# Sheet1.net
KiCad netlist of a schematic drawn in Altium Designer
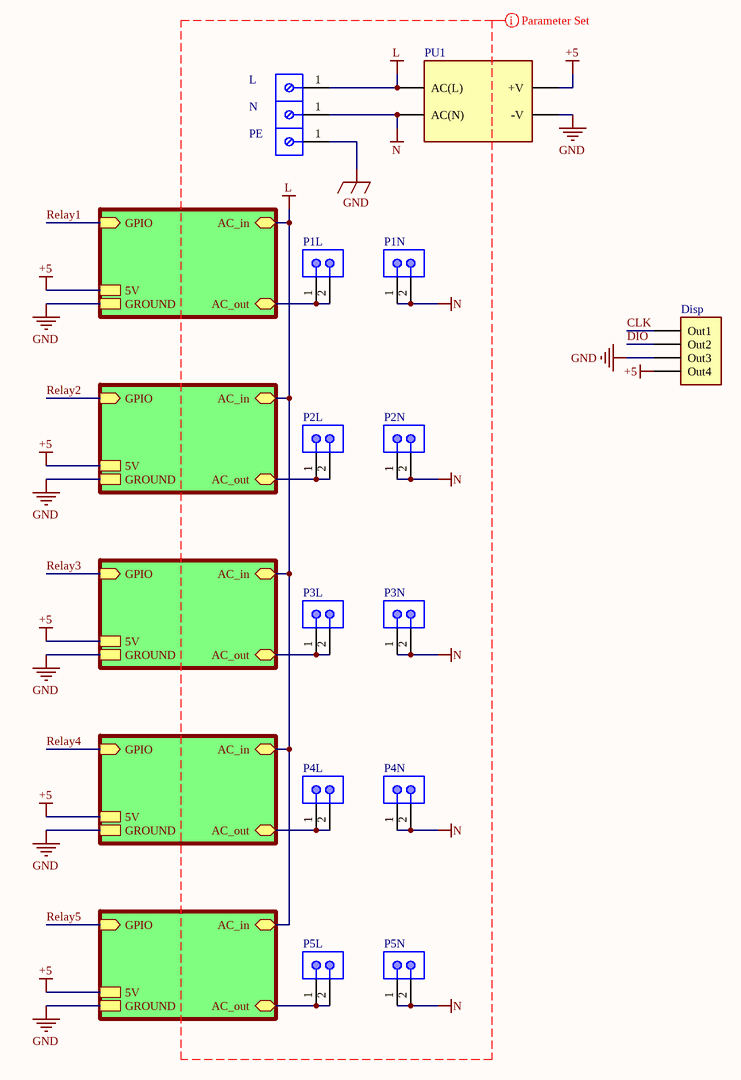
[diagram p0: Sheet1.SchDoc]

(export (version "E")
  (design (tool "Eeschema 10.0.6"))
  (components
    (comp (ref "Disp")
      (value "4Pin Connector")
      (footprint "4Pin Connector")
      (libsource (lib "Schlib1") (part "4Pin Connector"))
    )
    (comp (ref "L")
      (value "691102810001")
      (footprint "691102810001")
      (libsource (lib "Altium Content Vault") (part "TBL - 1R - 01P - Screw"))
    )
    (comp (ref "N")
      (value "691102810001")
      (footprint "691102810001")
      (libsource (lib "Altium Content Vault") (part "TBL - 1R - 01P - Screw"))
    )
    (comp (ref "P1L")
      (value "1287-ST")
      (footprint "KSTN-1287-ST")
      (description "PC Sturdi-Mount Quick-Fit Terminal, Vertical, Male, 2-Pin THD, Bulk")
      (fields (field (name "MANUFACTURER") "Keystone"))
      (libsource (lib "Altium Content Vault") (part "CN-1P-M-R2"))
    )
    (comp (ref "P1N")
      (value "1287-ST")
      (footprint "KSTN-1287-ST")
      (description "PC Sturdi-Mount Quick-Fit Terminal, Vertical, Male, 2-Pin THD, Bulk")
      (fields (field (name "MANUFACTURER") "Keystone"))
      (libsource (lib "Altium Content Vault") (part "CN-1P-M-R2"))
    )
    (comp (ref "P2L")
      (value "1287-ST")
      (footprint "KSTN-1287-ST")
      (description "PC Sturdi-Mount Quick-Fit Terminal, Vertical, Male, 2-Pin THD, Bulk")
      (fields (field (name "MANUFACTURER") "Keystone"))
      (libsource (lib "Altium Content Vault") (part "CN-1P-M-R2"))
    )
    (comp (ref "P2N")
      (value "1287-ST")
      (footprint "KSTN-1287-ST")
      (description "PC Sturdi-Mount Quick-Fit Terminal, Vertical, Male, 2-Pin THD, Bulk")
      (fields (field (name "MANUFACTURER") "Keystone"))
      (libsource (lib "Altium Content Vault") (part "CN-1P-M-R2"))
    )
    (comp (ref "P3L")
      (value "1287-ST")
      (footprint "KSTN-1287-ST")
      (description "PC Sturdi-Mount Quick-Fit Terminal, Vertical, Male, 2-Pin THD, Bulk")
      (fields (field (name "MANUFACTURER") "Keystone"))
      (libsource (lib "Altium Content Vault") (part "CN-1P-M-R2"))
    )
    (comp (ref "P3N")
      (value "1287-ST")
      (footprint "KSTN-1287-ST")
      (description "PC Sturdi-Mount Quick-Fit Terminal, Vertical, Male, 2-Pin THD, Bulk")
      (fields (field (name "MANUFACTURER") "Keystone"))
      (libsource (lib "Altium Content Vault") (part "CN-1P-M-R2"))
    )
    (comp (ref "P4L")
      (value "1287-ST")
      (footprint "KSTN-1287-ST")
      (description "PC Sturdi-Mount Quick-Fit Terminal, Vertical, Male, 2-Pin THD, Bulk")
      (fields (field (name "MANUFACTURER") "Keystone"))
      (libsource (lib "Altium Content Vault") (part "CN-1P-M-R2"))
    )
    (comp (ref "P4N")
      (value "1287-ST")
      (footprint "KSTN-1287-ST")
      (description "PC Sturdi-Mount Quick-Fit Terminal, Vertical, Male, 2-Pin THD, Bulk")
      (fields (field (name "MANUFACTURER") "Keystone"))
      (libsource (lib "Altium Content Vault") (part "CN-1P-M-R2"))
    )
    (comp (ref "P5L")
      (value "1287-ST")
      (footprint "KSTN-1287-ST")
      (description "PC Sturdi-Mount Quick-Fit Terminal, Vertical, Male, 2-Pin THD, Bulk")
      (fields (field (name "MANUFACTURER") "Keystone"))
      (libsource (lib "Altium Content Vault") (part "CN-1P-M-R2"))
    )
    (comp (ref "P5N")
      (value "1287-ST")
      (footprint "KSTN-1287-ST")
      (description "PC Sturdi-Mount Quick-Fit Terminal, Vertical, Male, 2-Pin THD, Bulk")
      (fields (field (name "MANUFACTURER") "Keystone"))
      (libsource (lib "Altium Content Vault") (part "CN-1P-M-R2"))
    )
    (comp (ref "PE")
      (value "691102810001")
      (footprint "691102810001")
      (libsource (lib "Altium Content Vault") (part "TBL - 1R - 01P - Screw"))
    )
    (comp (ref "PU1")
      (value "Netzteil")
      (footprint "Netzteil")
      (description "IRM-05-5")
      (libsource (lib "Schlib1") (part "Netzteil"))
    )
  )
  (nets
    (net (code "1") (name "+5") (class "Default")
      (node (ref "Disp") (pin "4") (pinfunction "Out4_4") (pintype "passive"))
      (node (ref "PU1") (pin "VPOS") (pinfunction "+V_VPOS") (pintype "passive"))
    )
    (net (code "2") (name "/AC_out") (class "Default")
      (node (ref "P5L") (pin "1") (pinfunction "1_1") (pintype "passive"))
      (node (ref "P5L") (pin "2") (pinfunction "2_2") (pintype "passive"))
    )
    (net (code "3") (name "/AC_out_1") (class "Default")
      (node (ref "P2L") (pin "1") (pinfunction "1_1") (pintype "passive"))
      (node (ref "P2L") (pin "2") (pinfunction "2_2") (pintype "passive"))
    )
    (net (code "4") (name "/AC_out_2") (class "Default")
      (node (ref "P1L") (pin "1") (pinfunction "1_1") (pintype "passive"))
      (node (ref "P1L") (pin "2") (pinfunction "2_2") (pintype "passive"))
    )
    (net (code "5") (name "/AC_out_3") (class "Default")
      (node (ref "P3L") (pin "1") (pinfunction "1_1") (pintype "passive"))
      (node (ref "P3L") (pin "2") (pinfunction "2_2") (pintype "passive"))
    )
    (net (code "6") (name "/AC_out_4") (class "Default")
      (node (ref "P4L") (pin "1") (pinfunction "1_1") (pintype "passive"))
      (node (ref "P4L") (pin "2") (pinfunction "2_2") (pintype "passive"))
    )
    (net (code "7") (name "/CLK") (class "Default")
      (node (ref "Disp") (pin "1") (pinfunction "Out1_1") (pintype "passive"))
    )
    (net (code "8") (name "/DIO") (class "Default")
      (node (ref "Disp") (pin "2") (pinfunction "Out2_2") (pintype "passive"))
    )
    (net (code "14") (name "GND") (class "Default")
      (node (ref "Disp") (pin "3") (pinfunction "Out3_3") (pintype "passive"))
      (node (ref "PE") (pin "1") (pinfunction "1_1") (pintype "passive"))
      (node (ref "PU1") (pin "VNEG") (pinfunction "-V_VNEG") (pintype "passive"))
    )
    (net (code "15") (name "L") (class "Default")
      (node (ref "L") (pin "1") (pinfunction "1_1") (pintype "passive"))
      (node (ref "PU1") (pin "AC/L") (pinfunction "AC(L)_AC/L") (pintype "passive"))
    )
    (net (code "16") (name "N") (class "Default")
      (node (ref "N") (pin "1") (pinfunction "1_1") (pintype "passive"))
      (node (ref "P1N") (pin "1") (pinfunction "1_1") (pintype "passive"))
      (node (ref "P1N") (pin "2") (pinfunction "2_2") (pintype "passive"))
      (node (ref "P2N") (pin "1") (pinfunction "1_1") (pintype "passive"))
      (node (ref "P2N") (pin "2") (pinfunction "2_2") (pintype "passive"))
      (node (ref "P3N") (pin "1") (pinfunction "1_1") (pintype "passive"))
      (node (ref "P3N") (pin "2") (pinfunction "2_2") (pintype "passive"))
      (node (ref "P4N") (pin "1") (pinfunction "1_1") (pintype "passive"))
      (node (ref "P4N") (pin "2") (pinfunction "2_2") (pintype "passive"))
      (node (ref "P5N") (pin "1") (pinfunction "1_1") (pintype "passive"))
      (node (ref "P5N") (pin "2") (pinfunction "2_2") (pintype "passive"))
      (node (ref "PU1") (pin "AC/N") (pinfunction "AC(N)_AC/N") (pintype "passive"))
    )
  )
)
